# 55percent.net
KiCad netlist of a schematic drawn in EAGLE
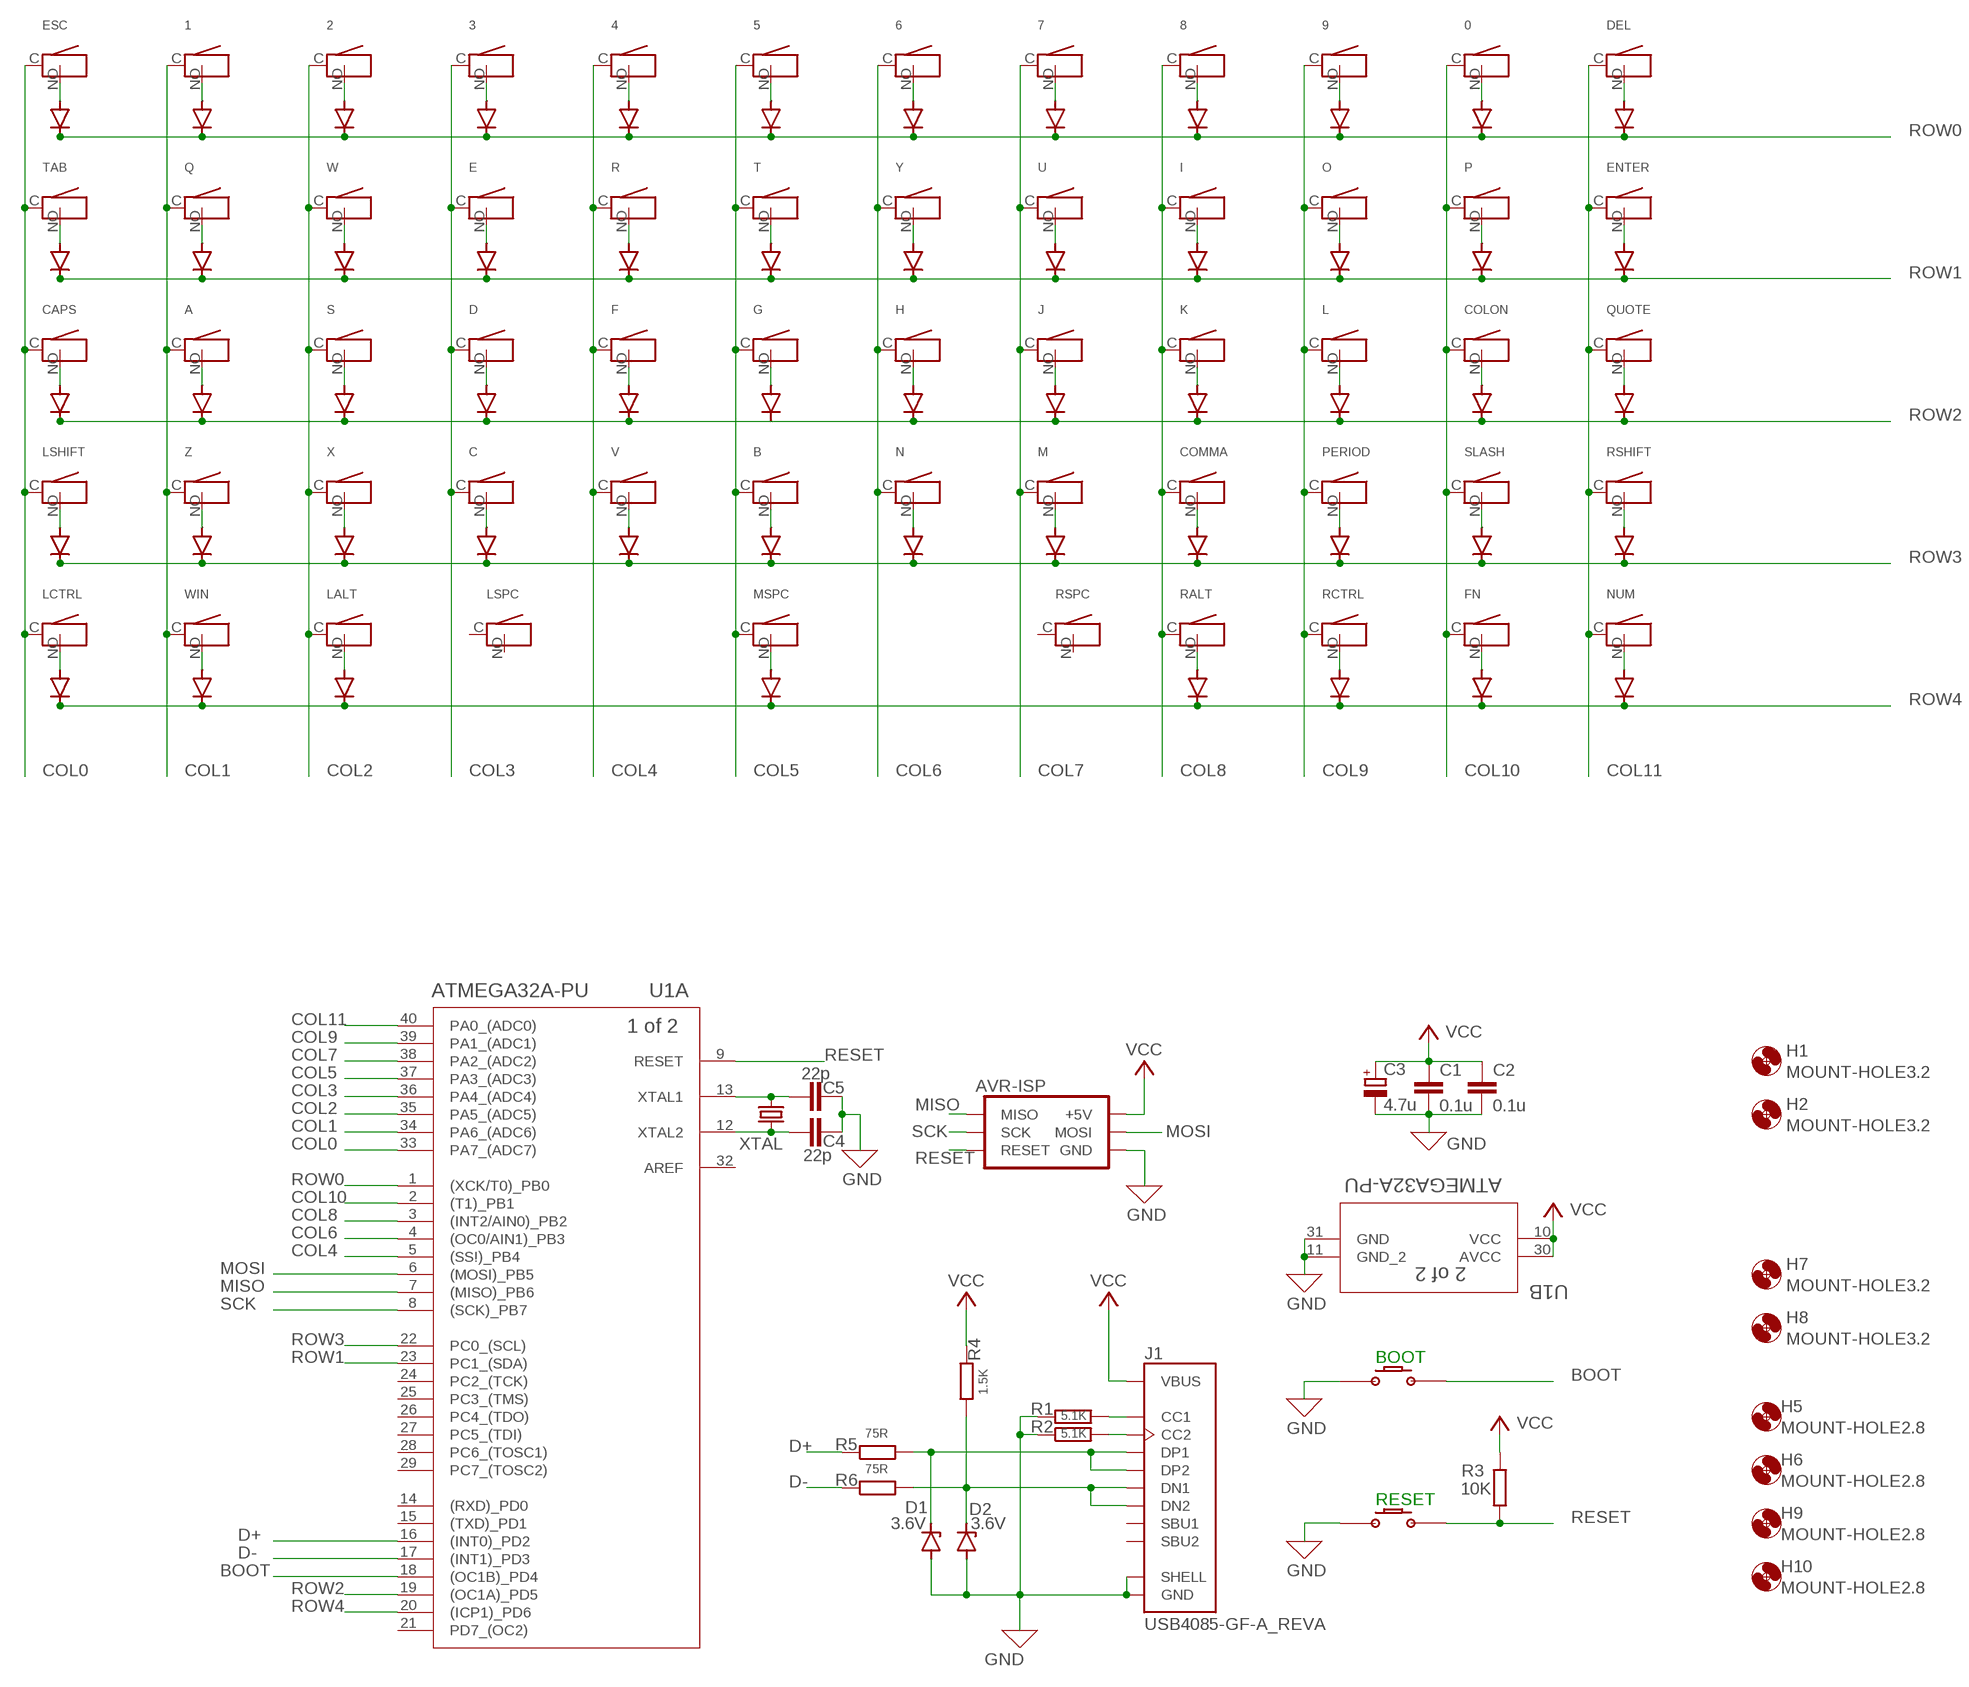
[diagram p0: schematic, sheet 1]

(export (version "E")
  (design (tool "Eeschema 10.0.6"))
  (components
    (comp (ref "0")
      (value "D2F_MICROSWITCH")
      (footprint "eagle-import:D2F_MICROSWITCH")
      (libsource (lib "eagle-import") (part "D2F_MICROSWITCH"))
    )
    (comp (ref "1")
      (value "D2F_MICROSWITCH")
      (footprint "eagle-import:D2F_MICROSWITCH")
      (libsource (lib "eagle-import") (part "D2F_MICROSWITCH"))
    )
    (comp (ref "2")
      (value "D2F_MICROSWITCH")
      (footprint "eagle-import:D2F_MICROSWITCH")
      (libsource (lib "eagle-import") (part "D2F_MICROSWITCH"))
    )
    (comp (ref "3")
      (value "D2F_MICROSWITCH")
      (footprint "eagle-import:D2F_MICROSWITCH")
      (libsource (lib "eagle-import") (part "D2F_MICROSWITCH"))
    )
    (comp (ref "4")
      (value "D2F_MICROSWITCH")
      (footprint "eagle-import:D2F_MICROSWITCH")
      (libsource (lib "eagle-import") (part "D2F_MICROSWITCH"))
    )
    (comp (ref "5")
      (value "D2F_MICROSWITCH")
      (footprint "eagle-import:D2F_MICROSWITCH")
      (libsource (lib "eagle-import") (part "D2F_MICROSWITCH"))
    )
    (comp (ref "6")
      (value "D2F_MICROSWITCH")
      (footprint "eagle-import:D2F_MICROSWITCH")
      (libsource (lib "eagle-import") (part "D2F_MICROSWITCH"))
    )
    (comp (ref "7")
      (value "D2F_MICROSWITCH")
      (footprint "eagle-import:D2F_MICROSWITCH")
      (libsource (lib "eagle-import") (part "D2F_MICROSWITCH"))
    )
    (comp (ref "8")
      (value "D2F_MICROSWITCH")
      (footprint "eagle-import:D2F_MICROSWITCH")
      (libsource (lib "eagle-import") (part "D2F_MICROSWITCH"))
    )
    (comp (ref "9")
      (value "D2F_MICROSWITCH")
      (footprint "eagle-import:D2F_MICROSWITCH")
      (libsource (lib "eagle-import") (part "D2F_MICROSWITCH"))
    )
    (comp (ref "A")
      (value "D2F_MICROSWITCH")
      (footprint "eagle-import:D2F_MICROSWITCH")
      (libsource (lib "eagle-import") (part "D2F_MICROSWITCH"))
    )
    (comp (ref "B")
      (value "D2F_MICROSWITCH")
      (footprint "eagle-import:D2F_MICROSWITCH")
      (libsource (lib "eagle-import") (part "D2F_MICROSWITCH"))
    )
    (comp (ref "C")
      (value "D2F_MICROSWITCH")
      (footprint "eagle-import:D2F_MICROSWITCH")
      (libsource (lib "eagle-import") (part "D2F_MICROSWITCH"))
    )
    (comp (ref "C1")
      (value "0.1u")
      (footprint "eagle-import:C025-024X044")
      (libsource (lib "eagle-import") (part "C-EU025-024X044"))
    )
    (comp (ref "C2")
      (value "0.1u")
      (footprint "eagle-import:C025-024X044")
      (libsource (lib "eagle-import") (part "C-EU025-024X044"))
    )
    (comp (ref "C3")
      (value "4.7u")
      (footprint "eagle-import:E2,5-5")
      (libsource (lib "eagle-import") (part "CPOL-EUE2.5-5"))
    )
    (comp (ref "C4")
      (value "22p")
      (footprint "eagle-import:C025-024X044")
      (libsource (lib "eagle-import") (part "C-EU025-024X044"))
    )
    (comp (ref "C5")
      (value "22p")
      (footprint "eagle-import:C025-024X044")
      (libsource (lib "eagle-import") (part "C-EU025-024X044"))
    )
    (comp (ref "CAPS")
      (value "D2F_MICROSWITCH")
      (footprint "eagle-import:D2F_MICROSWITCH")
      (libsource (lib "eagle-import") (part "D2F_MICROSWITCH"))
    )
    (comp (ref "COLON")
      (value "D2F_MICROSWITCH")
      (footprint "eagle-import:D2F_MICROSWITCH")
      (libsource (lib "eagle-import") (part "D2F_MICROSWITCH"))
    )
    (comp (ref "COMMA")
      (value "D2F_MICROSWITCH")
      (footprint "eagle-import:D2F_MICROSWITCH")
      (libsource (lib "eagle-import") (part "D2F_MICROSWITCH"))
    )
    (comp (ref "D")
      (value "D2F_MICROSWITCH")
      (footprint "eagle-import:D2F_MICROSWITCH")
      (libsource (lib "eagle-import") (part "D2F_MICROSWITCH"))
    )
    (comp (ref "D1")
      (value "3.6V")
      (footprint "eagle-import:DO34Z7")
      (libsource (lib "eagle-import") (part "BZV10"))
    )
    (comp (ref "D2")
      (value "3.6V")
      (footprint "eagle-import:DO34Z7")
      (libsource (lib "eagle-import") (part "BZV10"))
    )
    (comp (ref "D3")
      (value "1N4004")
      (footprint "eagle-import:DO41-10")
      (libsource (lib "eagle-import") (part "1N4004"))
    )
    (comp (ref "D4")
      (value "1N4004")
      (footprint "eagle-import:DO41-10")
      (libsource (lib "eagle-import") (part "1N4004"))
    )
    (comp (ref "D5")
      (value "1N4004")
      (footprint "eagle-import:DO41-10")
      (libsource (lib "eagle-import") (part "1N4004"))
    )
    (comp (ref "D6")
      (value "1N4004")
      (footprint "eagle-import:DO41-10")
      (libsource (lib "eagle-import") (part "1N4004"))
    )
    (comp (ref "D7")
      (value "1N4004")
      (footprint "eagle-import:DO41-10")
      (libsource (lib "eagle-import") (part "1N4004"))
    )
    (comp (ref "D8")
      (value "1N4004")
      (footprint "eagle-import:DO41-10")
      (libsource (lib "eagle-import") (part "1N4004"))
    )
    (comp (ref "D9")
      (value "1N4004")
      (footprint "eagle-import:DO41-10")
      (libsource (lib "eagle-import") (part "1N4004"))
    )
    (comp (ref "D10")
      (value "1N4004")
      (footprint "eagle-import:DO41-10")
      (libsource (lib "eagle-import") (part "1N4004"))
    )
    (comp (ref "D11")
      (value "1N4004")
      (footprint "eagle-import:DO41-10")
      (libsource (lib "eagle-import") (part "1N4004"))
    )
    (comp (ref "D12")
      (value "1N4004")
      (footprint "eagle-import:DO41-10")
      (libsource (lib "eagle-import") (part "1N4004"))
    )
    (comp (ref "D13")
      (value "1N4004")
      (footprint "eagle-import:DO41-10")
      (libsource (lib "eagle-import") (part "1N4004"))
    )
    (comp (ref "D14")
      (value "1N4004")
      (footprint "eagle-import:DO41-10")
      (libsource (lib "eagle-import") (part "1N4004"))
    )
    (comp (ref "D15")
      (value "1N4004")
      (footprint "eagle-import:DO41-10")
      (libsource (lib "eagle-import") (part "1N4004"))
    )
    (comp (ref "D16")
      (value "1N4004")
      (footprint "eagle-import:DO41-10")
      (libsource (lib "eagle-import") (part "1N4004"))
    )
    (comp (ref "D17")
      (value "1N4004")
      (footprint "eagle-import:DO41-10")
      (libsource (lib "eagle-import") (part "1N4004"))
    )
    (comp (ref "D18")
      (value "1N4004")
      (footprint "eagle-import:DO41-10")
      (libsource (lib "eagle-import") (part "1N4004"))
    )
    (comp (ref "D19")
      (value "1N4004")
      (footprint "eagle-import:DO41-10")
      (libsource (lib "eagle-import") (part "1N4004"))
    )
    (comp (ref "D20")
      (value "1N4004")
      (footprint "eagle-import:DO41-10")
      (libsource (lib "eagle-import") (part "1N4004"))
    )
    (comp (ref "D21")
      (value "1N4004")
      (footprint "eagle-import:DO41-10")
      (libsource (lib "eagle-import") (part "1N4004"))
    )
    (comp (ref "D23")
      (value "1N4004")
      (footprint "eagle-import:DO41-10")
      (libsource (lib "eagle-import") (part "1N4004"))
    )
    (comp (ref "D24")
      (value "1N4004")
      (footprint "eagle-import:DO41-10")
      (libsource (lib "eagle-import") (part "1N4004"))
    )
    (comp (ref "D25")
      (value "1N4004")
      (footprint "eagle-import:DO41-10")
      (libsource (lib "eagle-import") (part "1N4004"))
    )
    (comp (ref "D26")
      (value "1N4004")
      (footprint "eagle-import:DO41-10")
      (libsource (lib "eagle-import") (part "1N4004"))
    )
    (comp (ref "D28")
      (value "1N4004")
      (footprint "eagle-import:DO41-10")
      (libsource (lib "eagle-import") (part "1N4004"))
    )
    (comp (ref "D29")
      (value "1N4004")
      (footprint "eagle-import:DO41-10")
      (libsource (lib "eagle-import") (part "1N4004"))
    )
    (comp (ref "D30")
      (value "1N4004")
      (footprint "eagle-import:DO41-10")
      (libsource (lib "eagle-import") (part "1N4004"))
    )
    (comp (ref "D31")
      (value "1N4004")
      (footprint "eagle-import:DO41-10")
      (libsource (lib "eagle-import") (part "1N4004"))
    )
    (comp (ref "D32")
      (value "1N4004")
      (footprint "eagle-import:DO41-10")
      (libsource (lib "eagle-import") (part "1N4004"))
    )
    (comp (ref "D33")
      (value "1N4004")
      (footprint "eagle-import:DO41-10")
      (libsource (lib "eagle-import") (part "1N4004"))
    )
    (comp (ref "D34")
      (value "1N4004")
      (footprint "eagle-import:DO41-10")
      (libsource (lib "eagle-import") (part "1N4004"))
    )
    (comp (ref "D35")
      (value "1N4004")
      (footprint "eagle-import:DO41-10")
      (libsource (lib "eagle-import") (part "1N4004"))
    )
    (comp (ref "D36")
      (value "1N4004")
      (footprint "eagle-import:DO41-10")
      (libsource (lib "eagle-import") (part "1N4004"))
    )
    (comp (ref "D38")
      (value "1N4004")
      (footprint "eagle-import:DO41-10")
      (libsource (lib "eagle-import") (part "1N4004"))
    )
    (comp (ref "D39")
      (value "1N4004")
      (footprint "eagle-import:DO41-10")
      (libsource (lib "eagle-import") (part "1N4004"))
    )
    (comp (ref "D40")
      (value "1N4004")
      (footprint "eagle-import:DO41-10")
      (libsource (lib "eagle-import") (part "1N4004"))
    )
    (comp (ref "D41")
      (value "1N4004")
      (footprint "eagle-import:DO41-10")
      (libsource (lib "eagle-import") (part "1N4004"))
    )
    (comp (ref "D43")
      (value "1N4004")
      (footprint "eagle-import:DO41-10")
      (libsource (lib "eagle-import") (part "1N4004"))
    )
    (comp (ref "D44")
      (value "1N4004")
      (footprint "eagle-import:DO41-10")
      (libsource (lib "eagle-import") (part "1N4004"))
    )
    (comp (ref "D45")
      (value "1N4004")
      (footprint "eagle-import:DO41-10")
      (libsource (lib "eagle-import") (part "1N4004"))
    )
    (comp (ref "D46")
      (value "1N4004")
      (footprint "eagle-import:DO41-10")
      (libsource (lib "eagle-import") (part "1N4004"))
    )
    (comp (ref "D47")
      (value "1N4004")
      (footprint "eagle-import:DO41-10")
      (libsource (lib "eagle-import") (part "1N4004"))
    )
    (comp (ref "D48")
      (value "1N4004")
      (footprint "eagle-import:DO41-10")
      (libsource (lib "eagle-import") (part "1N4004"))
    )
    (comp (ref "D49")
      (value "1N4004")
      (footprint "eagle-import:DO41-10")
      (libsource (lib "eagle-import") (part "1N4004"))
    )
    (comp (ref "D50")
      (value "1N4004")
      (footprint "eagle-import:DO41-10")
      (libsource (lib "eagle-import") (part "1N4004"))
    )
    (comp (ref "D51")
      (value "1N4004")
      (footprint "eagle-import:DO41-10")
      (libsource (lib "eagle-import") (part "1N4004"))
    )
    (comp (ref "D52")
      (value "1N4004")
      (footprint "eagle-import:DO41-10")
      (libsource (lib "eagle-import") (part "1N4004"))
    )
    (comp (ref "D53")
      (value "1N4004")
      (footprint "eagle-import:DO41-10")
      (libsource (lib "eagle-import") (part "1N4004"))
    )
    (comp (ref "D54")
      (value "1N4004")
      (footprint "eagle-import:DO41-10")
      (libsource (lib "eagle-import") (part "1N4004"))
    )
    (comp (ref "D55")
      (value "1N4004")
      (footprint "eagle-import:DO41-10")
      (libsource (lib "eagle-import") (part "1N4004"))
    )
    (comp (ref "D56")
      (value "1N4004")
      (footprint "eagle-import:DO41-10")
      (libsource (lib "eagle-import") (part "1N4004"))
    )
    (comp (ref "D57")
      (value "1N4004")
      (footprint "eagle-import:DO41-10")
      (libsource (lib "eagle-import") (part "1N4004"))
    )
    (comp (ref "D58")
      (value "1N4004")
      (footprint "eagle-import:DO41-10")
      (libsource (lib "eagle-import") (part "1N4004"))
    )
    (comp (ref "D59")
      (value "1N4004")
      (footprint "eagle-import:DO41-10")
      (libsource (lib "eagle-import") (part "1N4004"))
    )
    (comp (ref "D60")
      (value "1N4004")
      (footprint "eagle-import:DO41-10")
      (libsource (lib "eagle-import") (part "1N4004"))
    )
    (comp (ref "D61")
      (value "1N4004")
      (footprint "eagle-import:DO41-10")
      (libsource (lib "eagle-import") (part "1N4004"))
    )
    (comp (ref "D62")
      (value "1N4004")
      (footprint "eagle-import:DO41-10")
      (libsource (lib "eagle-import") (part "1N4004"))
    )
    (comp (ref "DEL")
      (value "D2F_MICROSWITCH")
      (footprint "eagle-import:D2F_MICROSWITCH")
      (libsource (lib "eagle-import") (part "D2F_MICROSWITCH"))
    )
    (comp (ref "E")
      (value "D2F_MICROSWITCH")
      (footprint "eagle-import:D2F_MICROSWITCH")
      (libsource (lib "eagle-import") (part "D2F_MICROSWITCH"))
    )
    (comp (ref "ENTER")
      (value "D2F_MICROSWITCH")
      (footprint "eagle-import:D2F_MICROSWITCH")
      (libsource (lib "eagle-import") (part "D2F_MICROSWITCH"))
    )
    (comp (ref "ESC")
      (value "D2F_MICROSWITCH")
      (footprint "eagle-import:D2F_MICROSWITCH")
      (libsource (lib "eagle-import") (part "D2F_MICROSWITCH"))
    )
    (comp (ref "F")
      (value "D2F_MICROSWITCH")
      (footprint "eagle-import:D2F_MICROSWITCH")
      (libsource (lib "eagle-import") (part "D2F_MICROSWITCH"))
    )
    (comp (ref "FN")
      (value "D2F_MICROSWITCH")
      (footprint "eagle-import:D2F_MICROSWITCH")
      (libsource (lib "eagle-import") (part "D2F_MICROSWITCH"))
    )
    (comp (ref "G")
      (value "D2F_MICROSWITCH")
      (footprint "eagle-import:D2F_MICROSWITCH")
      (libsource (lib "eagle-import") (part "D2F_MICROSWITCH"))
    )
    (comp (ref "H")
      (value "D2F_MICROSWITCH")
      (footprint "eagle-import:D2F_MICROSWITCH")
      (libsource (lib "eagle-import") (part "D2F_MICROSWITCH"))
    )
    (comp (ref "H1")
      (value "MOUNT-HOLE3.2")
      (footprint "eagle-import:3,2")
      (libsource (lib "eagle-import") (part "MOUNT-HOLE3.2"))
    )
    (comp (ref "H2")
      (value "MOUNT-HOLE3.2")
      (footprint "eagle-import:3,2")
      (libsource (lib "eagle-import") (part "MOUNT-HOLE3.2"))
    )
    (comp (ref "H5")
      (value "MOUNT-HOLE2.8")
      (footprint "eagle-import:2,2")
      (libsource (lib "eagle-import") (part "MOUNT-HOLE2.8"))
    )
    (comp (ref "H6")
      (value "MOUNT-HOLE2.8")
      (footprint "eagle-import:2,2")
      (libsource (lib "eagle-import") (part "MOUNT-HOLE2.8"))
    )
    (comp (ref "H7")
      (value "MOUNT-HOLE3.2")
      (footprint "eagle-import:3,2")
      (libsource (lib "eagle-import") (part "MOUNT-HOLE3.2"))
    )
    (comp (ref "H8")
      (value "MOUNT-HOLE3.2")
      (footprint "eagle-import:3,2")
      (libsource (lib "eagle-import") (part "MOUNT-HOLE3.2"))
    )
    (comp (ref "H9")
      (value "MOUNT-HOLE2.8")
      (footprint "eagle-import:2,2")
      (libsource (lib "eagle-import") (part "MOUNT-HOLE2.8"))
    )
    (comp (ref "H10")
      (value "MOUNT-HOLE2.8")
      (footprint "eagle-import:2,2")
      (libsource (lib "eagle-import") (part "MOUNT-HOLE2.8"))
    )
    (comp (ref "I")
      (value "D2F_MICROSWITCH")
      (footprint "eagle-import:D2F_MICROSWITCH")
      (libsource (lib "eagle-import") (part "D2F_MICROSWITCH"))
    )
    (comp (ref "J")
      (value "D2F_MICROSWITCH")
      (footprint "eagle-import:D2F_MICROSWITCH")
      (libsource (lib "eagle-import") (part "D2F_MICROSWITCH"))
    )
    (comp (ref "J1")
      (value "USB4085-GF-A_REVA")
      (footprint "eagle-import:GCT_USB4085-GF-A_REVA")
      (fields (field (name "MF") "Global Connector Technology") (field (name "MP") "USB4085-GF-A"))
      (libsource (lib "eagle-import") (part "USB4085-GF-A_REVA"))
    )
    (comp (ref "JP1")
      (value "PINHD-2X3")
      (footprint "eagle-import:2X03")
      (libsource (lib "eagle-import") (part "PINHD-2X3"))
    )
    (comp (ref "K")
      (value "D2F_MICROSWITCH")
      (footprint "eagle-import:D2F_MICROSWITCH")
      (libsource (lib "eagle-import") (part "D2F_MICROSWITCH"))
    )
    (comp (ref "L")
      (value "D2F_MICROSWITCH")
      (footprint "eagle-import:D2F_MICROSWITCH")
      (libsource (lib "eagle-import") (part "D2F_MICROSWITCH"))
    )
    (comp (ref "LALT")
      (value "D2F_MICROSWITCH")
      (footprint "eagle-import:D2F_MICROSWITCH")
      (libsource (lib "eagle-import") (part "D2F_MICROSWITCH"))
    )
    (comp (ref "LCTRL")
      (value "D2F_MICROSWITCH")
      (footprint "eagle-import:D2F_MICROSWITCH")
      (libsource (lib "eagle-import") (part "D2F_MICROSWITCH"))
    )
    (comp (ref "LSHIFT")
      (value "D2F_MICROSWITCH")
      (footprint "eagle-import:D2F_MICROSWITCH")
      (libsource (lib "eagle-import") (part "D2F_MICROSWITCH"))
    )
    (comp (ref "LSPC")
      (value "D2F_MICROSWITCH")
      (footprint "eagle-import:D2F_MICROSWITCH")
      (libsource (lib "eagle-import") (part "D2F_MICROSWITCH"))
    )
    (comp (ref "M")
      (value "D2F_MICROSWITCH")
      (footprint "eagle-import:D2F_MICROSWITCH")
      (libsource (lib "eagle-import") (part "D2F_MICROSWITCH"))
    )
    (comp (ref "MSPC")
      (value "D2F_MICROSWITCH")
      (footprint "eagle-import:D2F_MICROSWITCH")
      (libsource (lib "eagle-import") (part "D2F_MICROSWITCH"))
    )
    (comp (ref "N")
      (value "D2F_MICROSWITCH")
      (footprint "eagle-import:D2F_MICROSWITCH")
      (libsource (lib "eagle-import") (part "D2F_MICROSWITCH"))
    )
    (comp (ref "NUM")
      (value "D2F_MICROSWITCH")
      (footprint "eagle-import:D2F_MICROSWITCH")
      (libsource (lib "eagle-import") (part "D2F_MICROSWITCH"))
    )
    (comp (ref "O")
      (value "D2F_MICROSWITCH")
      (footprint "eagle-import:D2F_MICROSWITCH")
      (libsource (lib "eagle-import") (part "D2F_MICROSWITCH"))
    )
    (comp (ref "P")
      (value "D2F_MICROSWITCH")
      (footprint "eagle-import:D2F_MICROSWITCH")
      (libsource (lib "eagle-import") (part "D2F_MICROSWITCH"))
    )
    (comp (ref "PERIOD")
      (value "D2F_MICROSWITCH")
      (footprint "eagle-import:D2F_MICROSWITCH")
      (libsource (lib "eagle-import") (part "D2F_MICROSWITCH"))
    )
    (comp (ref "Q")
      (value "D2F_MICROSWITCH")
      (footprint "eagle-import:D2F_MICROSWITCH")
      (libsource (lib "eagle-import") (part "D2F_MICROSWITCH"))
    )
    (comp (ref "QUOTE")
      (value "D2F_MICROSWITCH")
      (footprint "eagle-import:D2F_MICROSWITCH")
      (libsource (lib "eagle-import") (part "D2F_MICROSWITCH"))
    )
    (comp (ref "R")
      (value "D2F_MICROSWITCH")
      (footprint "eagle-import:D2F_MICROSWITCH")
      (libsource (lib "eagle-import") (part "D2F_MICROSWITCH"))
    )
    (comp (ref "R1")
      (value "5.1K")
      (footprint "eagle-import:0207_10")
      (libsource (lib "eagle-import") (part "R-EU_0207/10"))
    )
    (comp (ref "R2")
      (value "5.1K")
      (footprint "eagle-import:0207_10")
      (libsource (lib "eagle-import") (part "R-EU_0207/10"))
    )
    (comp (ref "R3")
      (value "10K")
      (footprint "eagle-import:0207_10")
      (libsource (lib "eagle-import") (part "R-EU_0207/10"))
    )
    (comp (ref "R4")
      (value "1.5K")
      (footprint "eagle-import:0207_10")
      (libsource (lib "eagle-import") (part "R-EU_0207/10"))
    )
    (comp (ref "R5")
      (value "75R")
      (footprint "eagle-import:0207_10")
      (libsource (lib "eagle-import") (part "R-EU_0207/10"))
    )
    (comp (ref "R6")
      (value "75R")
      (footprint "eagle-import:0207_10")
      (libsource (lib "eagle-import") (part "R-EU_0207/10"))
    )
    (comp (ref "RALT")
      (value "D2F_MICROSWITCH")
      (footprint "eagle-import:D2F_MICROSWITCH")
      (libsource (lib "eagle-import") (part "D2F_MICROSWITCH"))
    )
    (comp (ref "RCTRL")
      (value "D2F_MICROSWITCH")
      (footprint "eagle-import:D2F_MICROSWITCH")
      (libsource (lib "eagle-import") (part "D2F_MICROSWITCH"))
    )
    (comp (ref "RSHIFT")
      (value "D2F_MICROSWITCH")
      (footprint "eagle-import:D2F_MICROSWITCH")
      (libsource (lib "eagle-import") (part "D2F_MICROSWITCH"))
    )
    (comp (ref "RSPC")
      (value "D2F_MICROSWITCH")
      (footprint "eagle-import:D2F_MICROSWITCH")
      (libsource (lib "eagle-import") (part "D2F_MICROSWITCH"))
    )
    (comp (ref "S")
      (value "D2F_MICROSWITCH")
      (footprint "eagle-import:D2F_MICROSWITCH")
      (libsource (lib "eagle-import") (part "D2F_MICROSWITCH"))
    )
    (comp (ref "SLASH")
      (value "D2F_MICROSWITCH")
      (footprint "eagle-import:D2F_MICROSWITCH")
      (libsource (lib "eagle-import") (part "D2F_MICROSWITCH"))
    )
    (comp (ref "T")
      (value "D2F_MICROSWITCH")
      (footprint "eagle-import:D2F_MICROSWITCH")
      (libsource (lib "eagle-import") (part "D2F_MICROSWITCH"))
    )
    (comp (ref "TAB")
      (value "D2F_MICROSWITCH")
      (footprint "eagle-import:D2F_MICROSWITCH")
      (libsource (lib "eagle-import") (part "D2F_MICROSWITCH"))
    )
    (comp (ref "U")
      (value "D2F_MICROSWITCH")
      (footprint "eagle-import:D2F_MICROSWITCH")
      (libsource (lib "eagle-import") (part "D2F_MICROSWITCH"))
    )
    (comp (ref "U$1")
      (value "PTS636SK43LFS")
      (footprint "eagle-import:PTS636SK43LFSTHT")
      (libsource (lib "eagle-import") (part "PTS636SK43LFS"))
    )
    (comp (ref "U$2")
      (value "PTS636SK43LFS")
      (footprint "eagle-import:PTS636SK43LFSTHT")
      (libsource (lib "eagle-import") (part "PTS636SK43LFS"))
    )
    (comp (ref "U1")
      (value "ATMEGA32A-PU")
      (footprint "eagle-import:40P6")
      (libsource (lib "eagle-import") (part "ATMEGA32A-PU"))
    )
    (comp (ref "V")
      (value "D2F_MICROSWITCH")
      (footprint "eagle-import:D2F_MICROSWITCH")
      (libsource (lib "eagle-import") (part "D2F_MICROSWITCH"))
    )
    (comp (ref "W")
      (value "D2F_MICROSWITCH")
      (footprint "eagle-import:D2F_MICROSWITCH")
      (libsource (lib "eagle-import") (part "D2F_MICROSWITCH"))
    )
    (comp (ref "WIN")
      (value "D2F_MICROSWITCH")
      (footprint "eagle-import:D2F_MICROSWITCH")
      (libsource (lib "eagle-import") (part "D2F_MICROSWITCH"))
    )
    (comp (ref "X")
      (value "D2F_MICROSWITCH")
      (footprint "eagle-import:D2F_MICROSWITCH")
      (libsource (lib "eagle-import") (part "D2F_MICROSWITCH"))
    )
    (comp (ref "XTAL")
      (value "CRYSTALHC49S")
      (footprint "eagle-import:HC49_S")
      (libsource (lib "eagle-import") (part "CRYSTALHC49S"))
    )
    (comp (ref "Y")
      (value "D2F_MICROSWITCH")
      (footprint "eagle-import:D2F_MICROSWITCH")
      (libsource (lib "eagle-import") (part "D2F_MICROSWITCH"))
    )
    (comp (ref "Z")
      (value "D2F_MICROSWITCH")
      (footprint "eagle-import:D2F_MICROSWITCH")
      (libsource (lib "eagle-import") (part "D2F_MICROSWITCH"))
    )
  )
  (nets
    (net (code "1") (name "/BOOT") (class "Default")
      (node (ref "U$1") (pin "P$2") (pinfunction "P$2_P$2") (pintype "bidirectional"))
      (node (ref "U1") (pin "18") (pinfunction "(OC1B)_PD4_18") (pintype "bidirectional"))
    )
    (net (code "2") (name "/COL0") (class "Default")
      (node (ref "CAPS") (pin "C") (pinfunction "C_C") (pintype "bidirectional"))
      (node (ref "ESC") (pin "C") (pinfunction "C_C") (pintype "bidirectional"))
      (node (ref "LCTRL") (pin "C") (pinfunction "C_C") (pintype "bidirectional"))
      (node (ref "LSHIFT") (pin "C") (pinfunction "C_C") (pintype "bidirectional"))
      (node (ref "TAB") (pin "C") (pinfunction "C_C") (pintype "bidirectional"))
      (node (ref "U1") (pin "33") (pinfunction "PA7_(ADC7)_33") (pintype "bidirectional"))
    )
    (net (code "3") (name "/COL1") (class "Default")
      (node (ref "1") (pin "C") (pinfunction "C_C") (pintype "bidirectional"))
      (node (ref "A") (pin "C") (pinfunction "C_C") (pintype "bidirectional"))
      (node (ref "Q") (pin "C") (pinfunction "C_C") (pintype "bidirectional"))
      (node (ref "U1") (pin "34") (pinfunction "PA6_(ADC6)_34") (pintype "bidirectional"))
      (node (ref "WIN") (pin "C") (pinfunction "C_C") (pintype "bidirectional"))
      (node (ref "Z") (pin "C") (pinfunction "C_C") (pintype "bidirectional"))
    )
    (net (code "4") (name "/COL2") (class "Default")
      (node (ref "2") (pin "C") (pinfunction "C_C") (pintype "bidirectional"))
      (node (ref "LALT") (pin "C") (pinfunction "C_C") (pintype "bidirectional"))
      (node (ref "S") (pin "C") (pinfunction "C_C") (pintype "bidirectional"))
      (node (ref "U1") (pin "35") (pinfunction "PA5_(ADC5)_35") (pintype "bidirectional"))
      (node (ref "W") (pin "C") (pinfunction "C_C") (pintype "bidirectional"))
      (node (ref "X") (pin "C") (pinfunction "C_C") (pintype "bidirectional"))
    )
    (net (code "5") (name "/COL3") (class "Default")
      (node (ref "3") (pin "C") (pinfunction "C_C") (pintype "bidirectional"))
      (node (ref "C") (pin "C") (pinfunction "C_C") (pintype "bidirectional"))
      (node (ref "D") (pin "C") (pinfunction "C_C") (pintype "bidirectional"))
      (node (ref "E") (pin "C") (pinfunction "C_C") (pintype "bidirectional"))
      (node (ref "U1") (pin "36") (pinfunction "PA4_(ADC4)_36") (pintype "bidirectional"))
    )
    (net (code "6") (name "/COL4") (class "Default")
      (node (ref "4") (pin "C") (pinfunction "C_C") (pintype "bidirectional"))
      (node (ref "F") (pin "C") (pinfunction "C_C") (pintype "bidirectional"))
      (node (ref "R") (pin "C") (pinfunction "C_C") (pintype "bidirectional"))
      (node (ref "U1") (pin "5") (pinfunction "(SS~{})_PB4_5") (pintype "bidirectional"))
      (node (ref "V") (pin "C") (pinfunction "C_C") (pintype "bidirectional"))
    )
    (net (code "7") (name "/COL5") (class "Default")
      (node (ref "5") (pin "C") (pinfunction "C_C") (pintype "bidirectional"))
      (node (ref "B") (pin "C") (pinfunction "C_C") (pintype "bidirectional"))
      (node (ref "G") (pin "C") (pinfunction "C_C") (pintype "bidirectional"))
      (node (ref "MSPC") (pin "C") (pinfunction "C_C") (pintype "bidirectional"))
      (node (ref "T") (pin "C") (pinfunction "C_C") (pintype "bidirectional"))
      (node (ref "U1") (pin "37") (pinfunction "PA3_(ADC3)_37") (pintype "bidirectional"))
    )
    (net (code "8") (name "/COL6") (class "Default")
      (node (ref "6") (pin "C") (pinfunction "C_C") (pintype "bidirectional"))
      (node (ref "H") (pin "C") (pinfunction "C_C") (pintype "bidirectional"))
      (node (ref "N") (pin "C") (pinfunction "C_C") (pintype "bidirectional"))
      (node (ref "U1") (pin "4") (pinfunction "(OC0/AIN1)_PB3_4") (pintype "bidirectional"))
      (node (ref "Y") (pin "C") (pinfunction "C_C") (pintype "bidirectional"))
    )
    (net (code "9") (name "/COL7") (class "Default")
      (node (ref "7") (pin "C") (pinfunction "C_C") (pintype "bidirectional"))
      (node (ref "J") (pin "C") (pinfunction "C_C") (pintype "bidirectional"))
      (node (ref "M") (pin "C") (pinfunction "C_C") (pintype "bidirectional"))
      (node (ref "U") (pin "C") (pinfunction "C_C") (pintype "bidirectional"))
      (node (ref "U1") (pin "38") (pinfunction "PA2_(ADC2)_38") (pintype "bidirectional"))
    )
    (net (code "10") (name "/COL8") (class "Default")
      (node (ref "8") (pin "C") (pinfunction "C_C") (pintype "bidirectional"))
      (node (ref "COMMA") (pin "C") (pinfunction "C_C") (pintype "bidirectional"))
      (node (ref "I") (pin "C") (pinfunction "C_C") (pintype "bidirectional"))
      (node (ref "K") (pin "C") (pinfunction "C_C") (pintype "bidirectional"))
      (node (ref "RALT") (pin "C") (pinfunction "C_C") (pintype "bidirectional"))
      (node (ref "U1") (pin "3") (pinfunction "(INT2/AIN0)_PB2_3") (pintype "bidirectional"))
    )
    (net (code "11") (name "/COL9") (class "Default")
      (node (ref "9") (pin "C") (pinfunction "C_C") (pintype "bidirectional"))
      (node (ref "L") (pin "C") (pinfunction "C_C") (pintype "bidirectional"))
      (node (ref "O") (pin "C") (pinfunction "C_C") (pintype "bidirectional"))
      (node (ref "PERIOD") (pin "C") (pinfunction "C_C") (pintype "bidirectional"))
      (node (ref "RCTRL") (pin "C") (pinfunction "C_C") (pintype "bidirectional"))
      (node (ref "U1") (pin "39") (pinfunction "PA1_(ADC1)_39") (pintype "bidirectional"))
    )
    (net (code "12") (name "/COL10") (class "Default")
      (node (ref "0") (pin "C") (pinfunction "C_C") (pintype "bidirectional"))
      (node (ref "COLON") (pin "C") (pinfunction "C_C") (pintype "bidirectional"))
      (node (ref "FN") (pin "C") (pinfunction "C_C") (pintype "bidirectional"))
      (node (ref "P") (pin "C") (pinfunction "C_C") (pintype "bidirectional"))
      (node (ref "SLASH") (pin "C") (pinfunction "C_C") (pintype "bidirectional"))
      (node (ref "U1") (pin "2") (pinfunction "(T1)_PB1_2") (pintype "bidirectional"))
    )
    (net (code "13") (name "/COL11") (class "Default")
      (node (ref "DEL") (pin "C") (pinfunction "C_C") (pintype "bidirectional"))
      (node (ref "ENTER") (pin "C") (pinfunction "C_C") (pintype "bidirectional"))
      (node (ref "NUM") (pin "C") (pinfunction "C_C") (pintype "bidirectional"))
      (node (ref "QUOTE") (pin "C") (pinfunction "C_C") (pintype "bidirectional"))
      (node (ref "RSHIFT") (pin "C") (pinfunction "C_C") (pintype "bidirectional"))
      (node (ref "U1") (pin "40") (pinfunction "PA0_(ADC0)_40") (pintype "bidirectional"))
    )
    (net (code "14") (name "/D+") (class "Default")
      (node (ref "R5") (pin "1") (pinfunction "1_1") (pintype "passive"))
      (node (ref "U1") (pin "16") (pinfunction "(INT0)_PD2_16") (pintype "bidirectional"))
    )
    (net (code "15") (name "/D-") (class "Default")
      (node (ref "R6") (pin "1") (pinfunction "1_1") (pintype "passive"))
      (node (ref "U1") (pin "17") (pinfunction "(INT1)_PD3_17") (pintype "bidirectional"))
    )
    (net (code "16") (name "/MISO") (class "Default")
      (node (ref "JP1") (pin "MISO") (pinfunction "MISO_MISO") (pintype "passive"))
      (node (ref "U1") (pin "7") (pinfunction "(MISO)_PB6_7") (pintype "bidirectional"))
    )
    (net (code "17") (name "/MOSI") (class "Default")
      (node (ref "JP1") (pin "MOSI") (pinfunction "MOSI_MOSI") (pintype "passive"))
      (node (ref "U1") (pin "6") (pinfunction "(MOSI)_PB5_6") (pintype "bidirectional"))
    )
    (net (code "18") (name "/RESET") (class "Default")
      (node (ref "JP1") (pin "RESET") (pinfunction "RESET_RESET") (pintype "passive"))
      (node (ref "R3") (pin "1") (pinfunction "1_1") (pintype "passive"))
      (node (ref "U$2") (pin "P$2") (pinfunction "P$2_P$2") (pintype "bidirectional"))
      (node (ref "U1") (pin "9") (pinfunction "RESET_9") (pintype "input"))
    )
    (net (code "19") (name "/ROW0") (class "Default")
      (node (ref "D13") (pin "C") (pinfunction "C_C") (pintype "passive"))
      (node (ref "D18") (pin "C") (pinfunction "C_C") (pintype "passive"))
      (node (ref "D23") (pin "C") (pinfunction "C_C") (pintype "passive"))
      (node (ref "D28") (pin "C") (pinfunction "C_C") (pintype "passive"))
      (node (ref "D3") (pin "C") (pinfunction "C_C") (pintype "passive"))
      (node (ref "D33") (pin "C") (pinfunction "C_C") (pintype "passive"))
      (node (ref "D38") (pin "C") (pinfunction "C_C") (pintype "passive"))
      (node (ref "D43") (pin "C") (pinfunction "C_C") (pintype "passive"))
      (node (ref "D48") (pin "C") (pinfunction "C_C") (pintype "passive"))
      (node (ref "D53") (pin "C") (pinfunction "C_C") (pintype "passive"))
      (node (ref "D58") (pin "C") (pinfunction "C_C") (pintype "passive"))
      (node (ref "D8") (pin "C") (pinfunction "C_C") (pintype "passive"))
      (node (ref "U1") (pin "1") (pinfunction "(XCK/T0)_PB0_1") (pintype "bidirectional"))
    )
    (net (code "20") (name "/ROW1") (class "Default")
      (node (ref "D14") (pin "C") (pinfunction "C_C") (pintype "passive"))
      (node (ref "D19") (pin "C") (pinfunction "C_C") (pintype "passive"))
      (node (ref "D24") (pin "C") (pinfunction "C_C") (pintype "passive"))
      (node (ref "D29") (pin "C") (pinfunction "C_C") (pintype "passive"))
      (node (ref "D34") (pin "C") (pinfunction "C_C") (pintype "passive"))
      (node (ref "D39") (pin "C") (pinfunction "C_C") (pintype "passive"))
      (node (ref "D4") (pin "C") (pinfunction "C_C") (pintype "passive"))
      (node (ref "D44") (pin "C") (pinfunction "C_C") (pintype "passive"))
      (node (ref "D49") (pin "C") (pinfunction "C_C") (pintype "passive"))
      (node (ref "D54") (pin "C") (pinfunction "C_C") (pintype "passive"))
      (node (ref "D59") (pin "C") (pinfunction "C_C") (pintype "passive"))
      (node (ref "D9") (pin "C") (pinfunction "C_C") (pintype "passive"))
      (node (ref "U1") (pin "23") (pinfunction "PC1_(SDA)_23") (pintype "bidirectional"))
    )
    (net (code "21") (name "/ROW2") (class "Default")
      (node (ref "D10") (pin "C") (pinfunction "C_C") (pintype "passive"))
      (node (ref "D15") (pin "C") (pinfunction "C_C") (pintype "passive"))
      (node (ref "D20") (pin "C") (pinfunction "C_C") (pintype "passive"))
      (node (ref "D25") (pin "C") (pinfunction "C_C") (pintype "passive"))
      (node (ref "D30") (pin "C") (pinfunction "C_C") (pintype "passive"))
      (node (ref "D35") (pin "C") (pinfunction "C_C") (pintype "passive"))
      (node (ref "D40") (pin "C") (pinfunction "C_C") (pintype "passive"))
      (node (ref "D45") (pin "C") (pinfunction "C_C") (pintype "passive"))
      (node (ref "D5") (pin "C") (pinfunction "C_C") (pintype "passive"))
      (node (ref "D50") (pin "C") (pinfunction "C_C") (pintype "passive"))
      (node (ref "D55") (pin "C") (pinfunction "C_C") (pintype "passive"))
      (node (ref "D60") (pin "C") (pinfunction "C_C") (pintype "passive"))
      (node (ref "U1") (pin "19") (pinfunction "(OC1A)_PD5_19") (pintype "bidirectional"))
    )
    (net (code "22") (name "/ROW3") (class "Default")
      (node (ref "D11") (pin "C") (pinfunction "C_C") (pintype "passive"))
      (node (ref "D16") (pin "C") (pinfunction "C_C") (pintype "passive"))
      (node (ref "D21") (pin "C") (pinfunction "C_C") (pintype "passive"))
      (node (ref "D26") (pin "C") (pinfunction "C_C") (pintype "passive"))
      (node (ref "D31") (pin "C") (pinfunction "C_C") (pintype "passive"))
      (node (ref "D36") (pin "C") (pinfunction "C_C") (pintype "passive"))
      (node (ref "D41") (pin "C") (pinfunction "C_C") (pintype "passive"))
      (node (ref "D46") (pin "C") (pinfunction "C_C") (pintype "passive"))
      (node (ref "D51") (pin "C") (pinfunction "C_C") (pintype "passive"))
      (node (ref "D56") (pin "C") (pinfunction "C_C") (pintype "passive"))
      (node (ref "D6") (pin "C") (pinfunction "C_C") (pintype "passive"))
      (node (ref "D61") (pin "C") (pinfunction "C_C") (pintype "passive"))
      (node (ref "U1") (pin "22") (pinfunction "PC0_(SCL)_22") (pintype "bidirectional"))
    )
    (net (code "23") (name "/ROW4") (class "Default")
      (node (ref "D12") (pin "C") (pinfunction "C_C") (pintype "passive"))
      (node (ref "D17") (pin "C") (pinfunction "C_C") (pintype "passive"))
      (node (ref "D32") (pin "C") (pinfunction "C_C") (pintype "passive"))
      (node (ref "D47") (pin "C") (pinfunction "C_C") (pintype "passive"))
      (node (ref "D52") (pin "C") (pinfunction "C_C") (pintype "passive"))
      (node (ref "D57") (pin "C") (pinfunction "C_C") (pintype "passive"))
      (node (ref "D62") (pin "C") (pinfunction "C_C") (pintype "passive"))
      (node (ref "D7") (pin "C") (pinfunction "C_C") (pintype "passive"))
      (node (ref "U1") (pin "20") (pinfunction "(ICP1)_PD6_20") (pintype "bidirectional"))
    )
    (net (code "24") (name "/SCK") (class "Default")
      (node (ref "JP1") (pin "SCK") (pinfunction "SCK_SCK") (pintype "passive"))
      (node (ref "U1") (pin "8") (pinfunction "(SCK)_PB7_8") (pintype "bidirectional"))
    )
    (net (code "25") (name "GND") (class "Default")
      (node (ref "C1") (pin "2") (pinfunction "2_2") (pintype "passive"))
      (node (ref "C2") (pin "2") (pinfunction "2_2") (pintype "passive"))
      (node (ref "C3") (pin "-") (pinfunction "-_-") (pintype "passive"))
      (node (ref "C4") (pin "1") (pinfunction "1_1") (pintype "passive"))
      (node (ref "C5") (pin "1") (pinfunction "1_1") (pintype "passive"))
      (node (ref "D1") (pin "A") (pinfunction "A_A") (pintype "passive"))
      (node (ref "D2") (pin "A") (pinfunction "A_A") (pintype "passive"))
      (node (ref "J1") (pin "A1") (pinfunction "GND_A1") (pintype "passive"))
      (node (ref "J1") (pin "A12") (pinfunction "GND_A12") (pintype "passive"))
      (node (ref "J1") (pin "B1") (pinfunction "GND_B1") (pintype "passive"))
      (node (ref "J1") (pin "B12") (pinfunction "GND_B12") (pintype "passive"))
      (node (ref "J1") (pin "P1") (pinfunction "SHELL_P1") (pintype "passive"))
      (node (ref "J1") (pin "P2") (pinfunction "SHELL_P2") (pintype "passive"))
      (node (ref "J1") (pin "P3") (pinfunction "SHELL_P3") (pintype "passive"))
      (node (ref "J1") (pin "P4") (pinfunction "SHELL_P4") (pintype "passive"))
      (node (ref "JP1") (pin "GND") (pinfunction "GND_GND") (pintype "passive"))
      (node (ref "R1") (pin "1") (pinfunction "1_1") (pintype "passive"))
      (node (ref "R2") (pin "1") (pinfunction "1_1") (pintype "passive"))
      (node (ref "U$1") (pin "P$1") (pinfunction "P$1_P$1") (pintype "bidirectional"))
      (node (ref "U$2") (pin "P$1") (pinfunction "P$1_P$1") (pintype "bidirectional"))
      (node (ref "U1") (pin "11") (pinfunction "GND_2_11") (pintype "power_in"))
      (node (ref "U1") (pin "31") (pinfunction "GND_31") (pintype "power_in"))
    )
    (net (code "26") (name "Net-(0-O)") (class "Default")
      (node (ref "0") (pin "NO") (pinfunction "O_NO") (pintype "bidirectional"))
      (node (ref "D53") (pin "A") (pinfunction "A_A") (pintype "passive"))
    )
    (net (code "27") (name "Net-(1-O)") (class "Default")
      (node (ref "1") (pin "NO") (pinfunction "O_NO") (pintype "bidirectional"))
      (node (ref "D8") (pin "A") (pinfunction "A_A") (pintype "passive"))
    )
    (net (code "28") (name "Net-(2-O)") (class "Default")
      (node (ref "2") (pin "NO") (pinfunction "O_NO") (pintype "bidirectional"))
      (node (ref "D13") (pin "A") (pinfunction "A_A") (pintype "passive"))
    )
    (net (code "29") (name "Net-(3-O)") (class "Default")
      (node (ref "3") (pin "NO") (pinfunction "O_NO") (pintype "bidirectional"))
      (node (ref "D18") (pin "A") (pinfunction "A_A") (pintype "passive"))
    )
    (net (code "30") (name "Net-(4-O)") (class "Default")
      (node (ref "4") (pin "NO") (pinfunction "O_NO") (pintype "bidirectional"))
      (node (ref "D23") (pin "A") (pinfunction "A_A") (pintype "passive"))
    )
    (net (code "31") (name "Net-(5-O)") (class "Default")
      (node (ref "5") (pin "NO") (pinfunction "O_NO") (pintype "bidirectional"))
      (node (ref "D28") (pin "A") (pinfunction "A_A") (pintype "passive"))
    )
    (net (code "32") (name "Net-(6-O)") (class "Default")
      (node (ref "6") (pin "NO") (pinfunction "O_NO") (pintype "bidirectional"))
      (node (ref "D33") (pin "A") (pinfunction "A_A") (pintype "passive"))
    )
    (net (code "33") (name "Net-(7-O)") (class "Default")
      (node (ref "7") (pin "NO") (pinfunction "O_NO") (pintype "bidirectional"))
      (node (ref "D38") (pin "A") (pinfunction "A_A") (pintype "passive"))
    )
    (net (code "34") (name "Net-(8-O)") (class "Default")
      (node (ref "8") (pin "NO") (pinfunction "O_NO") (pintype "bidirectional"))
      (node (ref "D43") (pin "A") (pinfunction "A_A") (pintype "passive"))
    )
    (net (code "35") (name "Net-(9-O)") (class "Default")
      (node (ref "9") (pin "NO") (pinfunction "O_NO") (pintype "bidirectional"))
      (node (ref "D48") (pin "A") (pinfunction "A_A") (pintype "passive"))
    )
    (net (code "36") (name "Net-(A-O)") (class "Default")
      (node (ref "A") (pin "NO") (pinfunction "O_NO") (pintype "bidirectional"))
      (node (ref "D10") (pin "A") (pinfunction "A_A") (pintype "passive"))
    )
    (net (code "37") (name "Net-(B-O)") (class "Default")
      (node (ref "B") (pin "NO") (pinfunction "O_NO") (pintype "bidirectional"))
      (node (ref "D31") (pin "A") (pinfunction "A_A") (pintype "passive"))
    )
    (net (code "38") (name "Net-(C-O)") (class "Default")
      (node (ref "C") (pin "NO") (pinfunction "O_NO") (pintype "bidirectional"))
      (node (ref "D21") (pin "A") (pinfunction "A_A") (pintype "passive"))
    )
    (net (code "39") (name "Net-(CAPS-O)") (class "Default")
      (node (ref "CAPS") (pin "NO") (pinfunction "O_NO") (pintype "bidirectional"))
      (node (ref "D5") (pin "A") (pinfunction "A_A") (pintype "passive"))
    )
    (net (code "40") (name "Net-(COLON-O)") (class "Default")
      (node (ref "COLON") (pin "NO") (pinfunction "O_NO") (pintype "bidirectional"))
      (node (ref "D55") (pin "A") (pinfunction "A_A") (pintype "passive"))
    )
    (net (code "41") (name "Net-(COMMA-O)") (class "Default")
      (node (ref "COMMA") (pin "NO") (pinfunction "O_NO") (pintype "bidirectional"))
      (node (ref "D46") (pin "A") (pinfunction "A_A") (pintype "passive"))
    )
    (net (code "42") (name "Net-(D-O)") (class "Default")
      (node (ref "D") (pin "NO") (pinfunction "O_NO") (pintype "bidirectional"))
      (node (ref "D20") (pin "A") (pinfunction "A_A") (pintype "passive"))
    )
    (net (code "43") (name "Net-(DEL-O)") (class "Default")
      (node (ref "D58") (pin "A") (pinfunction "A_A") (pintype "passive"))
      (node (ref "DEL") (pin "NO") (pinfunction "O_NO") (pintype "bidirectional"))
    )
    (net (code "44") (name "Net-(E-O)") (class "Default")
      (node (ref "D19") (pin "A") (pinfunction "A_A") (pintype "passive"))
      (node (ref "E") (pin "NO") (pinfunction "O_NO") (pintype "bidirectional"))
    )
    (net (code "45") (name "Net-(ENTER-O)") (class "Default")
      (node (ref "D59") (pin "A") (pinfunction "A_A") (pintype "passive"))
      (node (ref "ENTER") (pin "NO") (pinfunction "O_NO") (pintype "bidirectional"))
    )
    (net (code "46") (name "Net-(ESC-O)") (class "Default")
      (node (ref "D3") (pin "A") (pinfunction "A_A") (pintype "passive"))
      (node (ref "ESC") (pin "NO") (pinfunction "O_NO") (pintype "bidirectional"))
    )
    (net (code "47") (name "Net-(F-O)") (class "Default")
      (node (ref "D25") (pin "A") (pinfunction "A_A") (pintype "passive"))
      (node (ref "F") (pin "NO") (pinfunction "O_NO") (pintype "bidirectional"))
    )
    (net (code "48") (name "Net-(FN-O)") (class "Default")
      (node (ref "D57") (pin "A") (pinfunction "A_A") (pintype "passive"))
      (node (ref "FN") (pin "NO") (pinfunction "O_NO") (pintype "bidirectional"))
    )
    (net (code "49") (name "Net-(G-O)") (class "Default")
      (node (ref "D30") (pin "A") (pinfunction "A_A") (pintype "passive"))
      (node (ref "G") (pin "NO") (pinfunction "O_NO") (pintype "bidirectional"))
    )
    (net (code "50") (name "Net-(H-O)") (class "Default")
      (node (ref "D35") (pin "A") (pinfunction "A_A") (pintype "passive"))
      (node (ref "H") (pin "NO") (pinfunction "O_NO") (pintype "bidirectional"))
    )
    (net (code "51") (name "Net-(I-O)") (class "Default")
      (node (ref "D44") (pin "A") (pinfunction "A_A") (pintype "passive"))
      (node (ref "I") (pin "NO") (pinfunction "O_NO") (pintype "bidirectional"))
    )
    (net (code "52") (name "Net-(J-O)") (class "Default")
      (node (ref "D40") (pin "A") (pinfunction "A_A") (pintype "passive"))
      (node (ref "J") (pin "NO") (pinfunction "O_NO") (pintype "bidirectional"))
    )
    (net (code "53") (name "Net-(J1-CC1)") (class "Default")
      (node (ref "J1") (pin "A5") (pinfunction "CC1_A5") (pintype "bidirectional"))
      (node (ref "R1") (pin "2") (pinfunction "2_2") (pintype "passive"))
    )
    (net (code "54") (name "Net-(J1-CC2)") (class "Default")
      (node (ref "J1") (pin "B5") (pinfunction "CC2_B5") (pintype "bidirectional"))
      (node (ref "R2") (pin "2") (pinfunction "2_2") (pintype "passive"))
    )
    (net (code "55") (name "Net-(J1-DN1)") (class "Default")
      (node (ref "D2") (pin "C") (pinfunction "C_C") (pintype "passive"))
      (node (ref "J1") (pin "A7") (pinfunction "DN1_A7") (pintype "bidirectional"))
      (node (ref "J1") (pin "B7") (pinfunction "DN2_B7") (pintype "bidirectional"))
      (node (ref "R4") (pin "2") (pinfunction "2_2") (pintype "passive"))
      (node (ref "R6") (pin "2") (pinfunction "2_2") (pintype "passive"))
    )
    (net (code "56") (name "Net-(J1-DP1)") (class "Default")
      (node (ref "D1") (pin "C") (pinfunction "C_C") (pintype "passive"))
      (node (ref "J1") (pin "A6") (pinfunction "DP1_A6") (pintype "bidirectional"))
      (node (ref "J1") (pin "B6") (pinfunction "DP2_B6") (pintype "bidirectional"))
      (node (ref "R5") (pin "2") (pinfunction "2_2") (pintype "passive"))
    )
    (net (code "57") (name "Net-(K-O)") (class "Default")
      (node (ref "D45") (pin "A") (pinfunction "A_A") (pintype "passive"))
      (node (ref "K") (pin "NO") (pinfunction "O_NO") (pintype "bidirectional"))
    )
    (net (code "58") (name "Net-(L-O)") (class "Default")
      (node (ref "D50") (pin "A") (pinfunction "A_A") (pintype "passive"))
      (node (ref "L") (pin "NO") (pinfunction "O_NO") (pintype "bidirectional"))
    )
    (net (code "59") (name "Net-(LALT-O)") (class "Default")
      (node (ref "D17") (pin "A") (pinfunction "A_A") (pintype "passive"))
      (node (ref "LALT") (pin "NO") (pinfunction "O_NO") (pintype "bidirectional"))
    )
    (net (code "60") (name "Net-(LCTRL-O)") (class "Default")
      (node (ref "D7") (pin "A") (pinfunction "A_A") (pintype "passive"))
      (node (ref "LCTRL") (pin "NO") (pinfunction "O_NO") (pintype "bidirectional"))
    )
    (net (code "61") (name "Net-(LSHIFT-O)") (class "Default")
      (node (ref "D6") (pin "A") (pinfunction "A_A") (pintype "passive"))
      (node (ref "LSHIFT") (pin "NO") (pinfunction "O_NO") (pintype "bidirectional"))
    )
    (net (code "62") (name "Net-(M-O)") (class "Default")
      (node (ref "D41") (pin "A") (pinfunction "A_A") (pintype "passive"))
      (node (ref "M") (pin "NO") (pinfunction "O_NO") (pintype "bidirectional"))
    )
    (net (code "63") (name "Net-(MSPC-O)") (class "Default")
      (node (ref "D32") (pin "A") (pinfunction "A_A") (pintype "passive"))
      (node (ref "MSPC") (pin "NO") (pinfunction "O_NO") (pintype "bidirectional"))
    )
    (net (code "64") (name "Net-(N-O)") (class "Default")
      (node (ref "D36") (pin "A") (pinfunction "A_A") (pintype "passive"))
      (node (ref "N") (pin "NO") (pinfunction "O_NO") (pintype "bidirectional"))
    )
    (net (code "65") (name "Net-(NUM-O)") (class "Default")
      (node (ref "D62") (pin "A") (pinfunction "A_A") (pintype "passive"))
      (node (ref "NUM") (pin "NO") (pinfunction "O_NO") (pintype "bidirectional"))
    )
    (net (code "66") (name "Net-(O-O)") (class "Default")
      (node (ref "D49") (pin "A") (pinfunction "A_A") (pintype "passive"))
      (node (ref "O") (pin "NO") (pinfunction "O_NO") (pintype "bidirectional"))
    )
    (net (code "67") (name "Net-(P-O)") (class "Default")
      (node (ref "D54") (pin "A") (pinfunction "A_A") (pintype "passive"))
      (node (ref "P") (pin "NO") (pinfunction "O_NO") (pintype "bidirectional"))
    )
    (net (code "68") (name "Net-(PERIOD-O)") (class "Default")
      (node (ref "D51") (pin "A") (pinfunction "A_A") (pintype "passive"))
      (node (ref "PERIOD") (pin "NO") (pinfunction "O_NO") (pintype "bidirectional"))
    )
    (net (code "69") (name "Net-(Q-O)") (class "Default")
      (node (ref "D9") (pin "A") (pinfunction "A_A") (pintype "passive"))
      (node (ref "Q") (pin "NO") (pinfunction "O_NO") (pintype "bidirectional"))
    )
    (net (code "70") (name "Net-(QUOTE-O)") (class "Default")
      (node (ref "D60") (pin "A") (pinfunction "A_A") (pintype "passive"))
      (node (ref "QUOTE") (pin "NO") (pinfunction "O_NO") (pintype "bidirectional"))
    )
    (net (code "71") (name "Net-(R-O)") (class "Default")
      (node (ref "D24") (pin "A") (pinfunction "A_A") (pintype "passive"))
      (node (ref "R") (pin "NO") (pinfunction "O_NO") (pintype "bidirectional"))
    )
    (net (code "72") (name "Net-(RALT-O)") (class "Default")
      (node (ref "D47") (pin "A") (pinfunction "A_A") (pintype "passive"))
      (node (ref "RALT") (pin "NO") (pinfunction "O_NO") (pintype "bidirectional"))
    )
    (net (code "73") (name "Net-(RCTRL-O)") (class "Default")
      (node (ref "D52") (pin "A") (pinfunction "A_A") (pintype "passive"))
      (node (ref "RCTRL") (pin "NO") (pinfunction "O_NO") (pintype "bidirectional"))
    )
    (net (code "74") (name "Net-(RSHIFT-O)") (class "Default")
      (node (ref "D61") (pin "A") (pinfunction "A_A") (pintype "passive"))
      (node (ref "RSHIFT") (pin "NO") (pinfunction "O_NO") (pintype "bidirectional"))
    )
    (net (code "75") (name "Net-(S-O)") (class "Default")
      (node (ref "D15") (pin "A") (pinfunction "A_A") (pintype "passive"))
      (node (ref "S") (pin "NO") (pinfunction "O_NO") (pintype "bidirectional"))
    )
    (net (code "76") (name "Net-(SLASH-O)") (class "Default")
      (node (ref "D56") (pin "A") (pinfunction "A_A") (pintype "passive"))
      (node (ref "SLASH") (pin "NO") (pinfunction "O_NO") (pintype "bidirectional"))
    )
    (net (code "77") (name "Net-(T-O)") (class "Default")
      (node (ref "D29") (pin "A") (pinfunction "A_A") (pintype "passive"))
      (node (ref "T") (pin "NO") (pinfunction "O_NO") (pintype "bidirectional"))
    )
    (net (code "78") (name "Net-(TAB-O)") (class "Default")
      (node (ref "D4") (pin "A") (pinfunction "A_A") (pintype "passive"))
      (node (ref "TAB") (pin "NO") (pinfunction "O_NO") (pintype "bidirectional"))
    )
    (net (code "79") (name "Net-(U-O)") (class "Default")
      (node (ref "D39") (pin "A") (pinfunction "A_A") (pintype "passive"))
      (node (ref "U") (pin "NO") (pinfunction "O_NO") (pintype "bidirectional"))
    )
    (net (code "80") (name "Net-(U1A-XTAL1)") (class "Default")
      (node (ref "C5") (pin "2") (pinfunction "2_2") (pintype "passive"))
      (node (ref "U1") (pin "13") (pinfunction "XTAL1_13") (pintype "input"))
      (node (ref "XTAL") (pin "1") (pinfunction "1_1") (pintype "passive"))
    )
    (net (code "81") (name "Net-(U1A-XTAL2)") (class "Default")
      (node (ref "C4") (pin "2") (pinfunction "2_2") (pintype "passive"))
      (node (ref "U1") (pin "12") (pinfunction "XTAL2_12") (pintype "output"))
      (node (ref "XTAL") (pin "2") (pinfunction "2_2") (pintype "passive"))
    )
    (net (code "82") (name "Net-(V-O)") (class "Default")
      (node (ref "D26") (pin "A") (pinfunction "A_A") (pintype "passive"))
      (node (ref "V") (pin "NO") (pinfunction "O_NO") (pintype "bidirectional"))
    )
    (net (code "83") (name "Net-(W-O)") (class "Default")
      (node (ref "D14") (pin "A") (pinfunction "A_A") (pintype "passive"))
      (node (ref "W") (pin "NO") (pinfunction "O_NO") (pintype "bidirectional"))
    )
    (net (code "84") (name "Net-(WIN-O)") (class "Default")
      (node (ref "D12") (pin "A") (pinfunction "A_A") (pintype "passive"))
      (node (ref "WIN") (pin "NO") (pinfunction "O_NO") (pintype "bidirectional"))
    )
    (net (code "85") (name "Net-(X-O)") (class "Default")
      (node (ref "D16") (pin "A") (pinfunction "A_A") (pintype "passive"))
      (node (ref "X") (pin "NO") (pinfunction "O_NO") (pintype "bidirectional"))
    )
    (net (code "86") (name "Net-(Y-O)") (class "Default")
      (node (ref "D34") (pin "A") (pinfunction "A_A") (pintype "passive"))
      (node (ref "Y") (pin "NO") (pinfunction "O_NO") (pintype "bidirectional"))
    )
    (net (code "87") (name "Net-(Z-O)") (class "Default")
      (node (ref "D11") (pin "A") (pinfunction "A_A") (pintype "passive"))
      (node (ref "Z") (pin "NO") (pinfunction "O_NO") (pintype "bidirectional"))
    )
    (net (code "88") (name "VCC") (class "Default")
      (node (ref "C1") (pin "1") (pinfunction "1_1") (pintype "passive"))
      (node (ref "C2") (pin "1") (pinfunction "1_1") (pintype "passive"))
      (node (ref "C3") (pin "+") (pinfunction "+_+") (pintype "passive"))
      (node (ref "J1") (pin "A4") (pinfunction "VBUS_A4") (pintype "power_in"))
      (node (ref "J1") (pin "A9") (pinfunction "VBUS_A9") (pintype "power_in"))
      (node (ref "J1") (pin "B4") (pinfunction "VBUS_B4") (pintype "power_in"))
      (node (ref "J1") (pin "B9") (pinfunction "VBUS_B9") (pintype "power_in"))
      (node (ref "JP1") (pin "+5V") (pinfunction "+5V_+5V") (pintype "passive"))
      (node (ref "R3") (pin "2") (pinfunction "2_2") (pintype "passive"))
      (node (ref "R4") (pin "1") (pinfunction "1_1") (pintype "passive"))
      (node (ref "U1") (pin "10") (pinfunction "VCC_10") (pintype "power_in"))
      (node (ref "U1") (pin "30") (pinfunction "AVCC_30") (pintype "power_in"))
    )
    (net (code "89") (name "unconnected-(0-PadNC)") (class "Default")
      (node (ref "0") (pin "NC") (pinfunction "NC_NC") (pintype "no_connect"))
    )
    (net (code "90") (name "unconnected-(1-PadNC)") (class "Default")
      (node (ref "1") (pin "NC") (pinfunction "NC_NC") (pintype "no_connect"))
    )
    (net (code "91") (name "unconnected-(2-PadNC)") (class "Default")
      (node (ref "2") (pin "NC") (pinfunction "NC_NC") (pintype "no_connect"))
    )
    (net (code "92") (name "unconnected-(3-PadNC)") (class "Default")
      (node (ref "3") (pin "NC") (pinfunction "NC_NC") (pintype "no_connect"))
    )
    (net (code "93") (name "unconnected-(4-PadNC)") (class "Default")
      (node (ref "4") (pin "NC") (pinfunction "NC_NC") (pintype "no_connect"))
    )
    (net (code "94") (name "unconnected-(5-PadNC)") (class "Default")
      (node (ref "5") (pin "NC") (pinfunction "NC_NC") (pintype "no_connect"))
    )
    (net (code "95") (name "unconnected-(6-PadNC)") (class "Default")
      (node (ref "6") (pin "NC") (pinfunction "NC_NC") (pintype "no_connect"))
    )
    (net (code "96") (name "unconnected-(7-PadNC)") (class "Default")
      (node (ref "7") (pin "NC") (pinfunction "NC_NC") (pintype "no_connect"))
    )
    (net (code "97") (name "unconnected-(8-PadNC)") (class "Default")
      (node (ref "8") (pin "NC") (pinfunction "NC_NC") (pintype "no_connect"))
    )
    (net (code "98") (name "unconnected-(9-PadNC)") (class "Default")
      (node (ref "9") (pin "NC") (pinfunction "NC_NC") (pintype "no_connect"))
    )
    (net (code "99") (name "unconnected-(A-PadNC)") (class "Default")
      (node (ref "A") (pin "NC") (pinfunction "NC_NC") (pintype "no_connect"))
    )
    (net (code "100") (name "unconnected-(B-PadNC)") (class "Default")
      (node (ref "B") (pin "NC") (pinfunction "NC_NC") (pintype "no_connect"))
    )
    (net (code "101") (name "unconnected-(C-PadNC)") (class "Default")
      (node (ref "C") (pin "NC") (pinfunction "NC_NC") (pintype "no_connect"))
    )
    (net (code "102") (name "unconnected-(CAPS-PadNC)") (class "Default")
      (node (ref "CAPS") (pin "NC") (pinfunction "NC_NC") (pintype "no_connect"))
    )
    (net (code "103") (name "unconnected-(COLON-PadNC)") (class "Default")
      (node (ref "COLON") (pin "NC") (pinfunction "NC_NC") (pintype "no_connect"))
    )
    (net (code "104") (name "unconnected-(COMMA-PadNC)") (class "Default")
      (node (ref "COMMA") (pin "NC") (pinfunction "NC_NC") (pintype "no_connect"))
    )
    (net (code "105") (name "unconnected-(D-PadNC)") (class "Default")
      (node (ref "D") (pin "NC") (pinfunction "NC_NC") (pintype "no_connect"))
    )
    (net (code "106") (name "unconnected-(DEL-PadNC)") (class "Default")
      (node (ref "DEL") (pin "NC") (pinfunction "NC_NC") (pintype "no_connect"))
    )
    (net (code "107") (name "unconnected-(E-PadNC)") (class "Default")
      (node (ref "E") (pin "NC") (pinfunction "NC_NC") (pintype "no_connect"))
    )
    (net (code "108") (name "unconnected-(ENTER-PadNC)") (class "Default")
      (node (ref "ENTER") (pin "NC") (pinfunction "NC_NC") (pintype "no_connect"))
    )
    (net (code "109") (name "unconnected-(ESC-PadNC)") (class "Default")
      (node (ref "ESC") (pin "NC") (pinfunction "NC_NC") (pintype "no_connect"))
    )
    (net (code "110") (name "unconnected-(F-PadNC)") (class "Default")
      (node (ref "F") (pin "NC") (pinfunction "NC_NC") (pintype "no_connect"))
    )
    (net (code "111") (name "unconnected-(FN-PadNC)") (class "Default")
      (node (ref "FN") (pin "NC") (pinfunction "NC_NC") (pintype "no_connect"))
    )
    (net (code "112") (name "unconnected-(G-PadNC)") (class "Default")
      (node (ref "G") (pin "NC") (pinfunction "NC_NC") (pintype "no_connect"))
    )
    (net (code "113") (name "unconnected-(H-PadNC)") (class "Default")
      (node (ref "H") (pin "NC") (pinfunction "NC_NC") (pintype "no_connect"))
    )
    (net (code "114") (name "unconnected-(I-PadNC)") (class "Default")
      (node (ref "I") (pin "NC") (pinfunction "NC_NC") (pintype "no_connect"))
    )
    (net (code "115") (name "unconnected-(J-PadNC)") (class "Default")
      (node (ref "J") (pin "NC") (pinfunction "NC_NC") (pintype "no_connect"))
    )
    (net (code "116") (name "unconnected-(J1-SBU1-PadA8)") (class "Default")
      (node (ref "J1") (pin "A8") (pinfunction "SBU1_A8") (pintype "bidirectional"))
    )
    (net (code "117") (name "unconnected-(J1-SBU2-PadB8)") (class "Default")
      (node (ref "J1") (pin "B8") (pinfunction "SBU2_B8") (pintype "bidirectional"))
    )
    (net (code "118") (name "unconnected-(K-PadNC)") (class "Default")
      (node (ref "K") (pin "NC") (pinfunction "NC_NC") (pintype "no_connect"))
    )
    (net (code "119") (name "unconnected-(L-PadNC)") (class "Default")
      (node (ref "L") (pin "NC") (pinfunction "NC_NC") (pintype "no_connect"))
    )
    (net (code "120") (name "unconnected-(LALT-PadNC)") (class "Default")
      (node (ref "LALT") (pin "NC") (pinfunction "NC_NC") (pintype "no_connect"))
    )
    (net (code "121") (name "unconnected-(LCTRL-PadNC)") (class "Default")
      (node (ref "LCTRL") (pin "NC") (pinfunction "NC_NC") (pintype "no_connect"))
    )
    (net (code "122") (name "unconnected-(LSHIFT-PadNC)") (class "Default")
      (node (ref "LSHIFT") (pin "NC") (pinfunction "NC_NC") (pintype "no_connect"))
    )
    (net (code "123") (name "unconnected-(LSPC-O-PadNO)") (class "Default")
      (node (ref "LSPC") (pin "NO") (pinfunction "O_NO") (pintype "bidirectional"))
    )
    (net (code "124") (name "unconnected-(LSPC-PadC)") (class "Default")
      (node (ref "LSPC") (pin "C") (pinfunction "C_C") (pintype "bidirectional"))
    )
    (net (code "125") (name "unconnected-(LSPC-PadNC)") (class "Default")
      (node (ref "LSPC") (pin "NC") (pinfunction "NC_NC") (pintype "no_connect"))
    )
    (net (code "126") (name "unconnected-(M-PadNC)") (class "Default")
      (node (ref "M") (pin "NC") (pinfunction "NC_NC") (pintype "no_connect"))
    )
    (net (code "127") (name "unconnected-(MSPC-PadNC)") (class "Default")
      (node (ref "MSPC") (pin "NC") (pinfunction "NC_NC") (pintype "no_connect"))
    )
    (net (code "128") (name "unconnected-(N-PadNC)") (class "Default")
      (node (ref "N") (pin "NC") (pinfunction "NC_NC") (pintype "no_connect"))
    )
    (net (code "129") (name "unconnected-(NUM-PadNC)") (class "Default")
      (node (ref "NUM") (pin "NC") (pinfunction "NC_NC") (pintype "no_connect"))
    )
    (net (code "130") (name "unconnected-(O-PadNC)") (class "Default")
      (node (ref "O") (pin "NC") (pinfunction "NC_NC") (pintype "no_connect"))
    )
    (net (code "131") (name "unconnected-(P-PadNC)") (class "Default")
      (node (ref "P") (pin "NC") (pinfunction "NC_NC") (pintype "no_connect"))
    )
    (net (code "132") (name "unconnected-(PERIOD-PadNC)") (class "Default")
      (node (ref "PERIOD") (pin "NC") (pinfunction "NC_NC") (pintype "no_connect"))
    )
    (net (code "133") (name "unconnected-(Q-PadNC)") (class "Default")
      (node (ref "Q") (pin "NC") (pinfunction "NC_NC") (pintype "no_connect"))
    )
    (net (code "134") (name "unconnected-(QUOTE-PadNC)") (class "Default")
      (node (ref "QUOTE") (pin "NC") (pinfunction "NC_NC") (pintype "no_connect"))
    )
    (net (code "135") (name "unconnected-(R-PadNC)") (class "Default")
      (node (ref "R") (pin "NC") (pinfunction "NC_NC") (pintype "no_connect"))
    )
    (net (code "136") (name "unconnected-(RALT-PadNC)") (class "Default")
      (node (ref "RALT") (pin "NC") (pinfunction "NC_NC") (pintype "no_connect"))
    )
    (net (code "137") (name "unconnected-(RCTRL-PadNC)") (class "Default")
      (node (ref "RCTRL") (pin "NC") (pinfunction "NC_NC") (pintype "no_connect"))
    )
    (net (code "138") (name "unconnected-(RSHIFT-PadNC)") (class "Default")
      (node (ref "RSHIFT") (pin "NC") (pinfunction "NC_NC") (pintype "no_connect"))
    )
    (net (code "139") (name "unconnected-(RSPC-O-PadNO)") (class "Default")
      (node (ref "RSPC") (pin "NO") (pinfunction "O_NO") (pintype "bidirectional"))
    )
    (net (code "140") (name "unconnected-(RSPC-PadC)") (class "Default")
      (node (ref "RSPC") (pin "C") (pinfunction "C_C") (pintype "bidirectional"))
    )
    (net (code "141") (name "unconnected-(RSPC-PadNC)") (class "Default")
      (node (ref "RSPC") (pin "NC") (pinfunction "NC_NC") (pintype "no_connect"))
    )
    (net (code "142") (name "unconnected-(S-PadNC)") (class "Default")
      (node (ref "S") (pin "NC") (pinfunction "NC_NC") (pintype "no_connect"))
    )
    (net (code "143") (name "unconnected-(SLASH-PadNC)") (class "Default")
      (node (ref "SLASH") (pin "NC") (pinfunction "NC_NC") (pintype "no_connect"))
    )
    (net (code "144") (name "unconnected-(T-PadNC)") (class "Default")
      (node (ref "T") (pin "NC") (pinfunction "NC_NC") (pintype "no_connect"))
    )
    (net (code "145") (name "unconnected-(TAB-PadNC)") (class "Default")
      (node (ref "TAB") (pin "NC") (pinfunction "NC_NC") (pintype "no_connect"))
    )
    (net (code "146") (name "unconnected-(U-PadNC)") (class "Default")
      (node (ref "U") (pin "NC") (pinfunction "NC_NC") (pintype "no_connect"))
    )
    (net (code "147") (name "unconnected-(U1A-(RXD)_PD0-Pad14)") (class "Default")
      (node (ref "U1") (pin "14") (pinfunction "(RXD)_PD0_14") (pintype "bidirectional"))
    )
    (net (code "148") (name "unconnected-(U1A-(TXD)_PD1-Pad15)") (class "Default")
      (node (ref "U1") (pin "15") (pinfunction "(TXD)_PD1_15") (pintype "bidirectional"))
    )
    (net (code "149") (name "unconnected-(U1A-AREF-Pad32)") (class "Default")
      (node (ref "U1") (pin "32") (pinfunction "AREF_32") (pintype "passive"))
    )
    (net (code "150") (name "unconnected-(U1A-PC2_(TCK)-Pad24)") (class "Default")
      (node (ref "U1") (pin "24") (pinfunction "PC2_(TCK)_24") (pintype "bidirectional"))
    )
    (net (code "151") (name "unconnected-(U1A-PC3_(TMS)-Pad25)") (class "Default")
      (node (ref "U1") (pin "25") (pinfunction "PC3_(TMS)_25") (pintype "bidirectional"))
    )
    (net (code "152") (name "unconnected-(U1A-PC4_(TDO)-Pad26)") (class "Default")
      (node (ref "U1") (pin "26") (pinfunction "PC4_(TDO)_26") (pintype "bidirectional"))
    )
    (net (code "153") (name "unconnected-(U1A-PC5_(TDI)-Pad27)") (class "Default")
      (node (ref "U1") (pin "27") (pinfunction "PC5_(TDI)_27") (pintype "bidirectional"))
    )
    (net (code "154") (name "unconnected-(U1A-PC6_(TOSC1)-Pad28)") (class "Default")
      (node (ref "U1") (pin "28") (pinfunction "PC6_(TOSC1)_28") (pintype "bidirectional"))
    )
    (net (code "155") (name "unconnected-(U1A-PC7_(TOSC2)-Pad29)") (class "Default")
      (node (ref "U1") (pin "29") (pinfunction "PC7_(TOSC2)_29") (pintype "bidirectional"))
    )
    (net (code "156") (name "unconnected-(U1A-PD7_(OC2)-Pad21)") (class "Default")
      (node (ref "U1") (pin "21") (pinfunction "PD7_(OC2)_21") (pintype "bidirectional"))
    )
    (net (code "157") (name "unconnected-(V-PadNC)") (class "Default")
      (node (ref "V") (pin "NC") (pinfunction "NC_NC") (pintype "no_connect"))
    )
    (net (code "158") (name "unconnected-(W-PadNC)") (class "Default")
      (node (ref "W") (pin "NC") (pinfunction "NC_NC") (pintype "no_connect"))
    )
    (net (code "159") (name "unconnected-(WIN-PadNC)") (class "Default")
      (node (ref "WIN") (pin "NC") (pinfunction "NC_NC") (pintype "no_connect"))
    )
    (net (code "160") (name "unconnected-(X-PadNC)") (class "Default")
      (node (ref "X") (pin "NC") (pinfunction "NC_NC") (pintype "no_connect"))
    )
    (net (code "161") (name "unconnected-(Y-PadNC)") (class "Default")
      (node (ref "Y") (pin "NC") (pinfunction "NC_NC") (pintype "no_connect"))
    )
    (net (code "162") (name "unconnected-(Z-PadNC)") (class "Default")
      (node (ref "Z") (pin "NC") (pinfunction "NC_NC") (pintype "no_connect"))
    )
  )
)
